# FoneAstra3_1.net
KiCad netlist of a schematic drawn in EAGLE
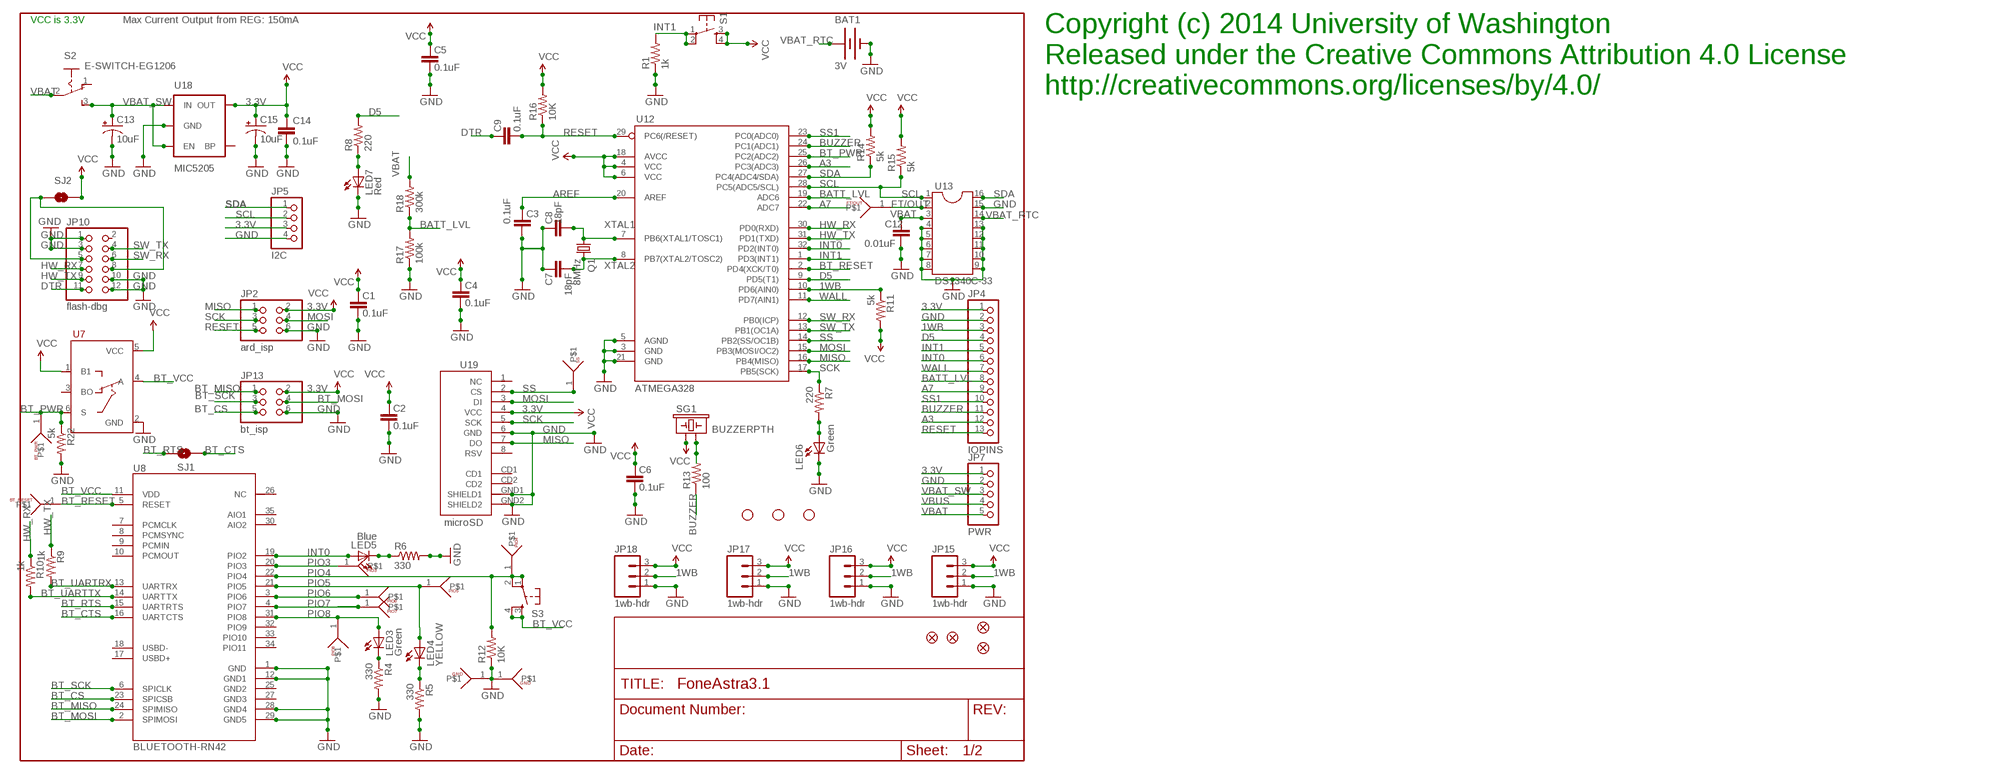
[diagram p0: schematic, sheet 1]
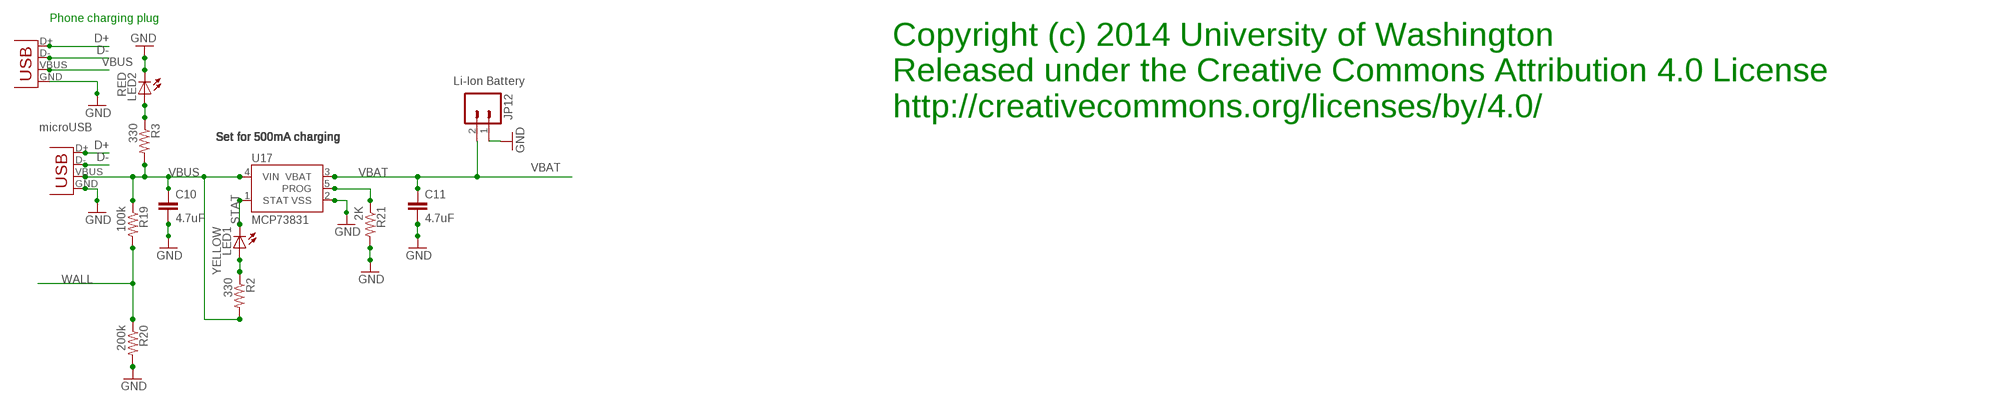
[diagram p1: schematic, sheet 2]

(export (version "E")
  (design (tool "Eeschema 10.0.6"))
  (components
    (comp (ref "$$U3")
      (value "BT_RESET")
      (footprint "eagle-import:TESTPOINT")
      (libsource (lib "eagle-import") (part "TESTPOINT"))
    )
    (comp (ref "$$U4")
      (value "PIO6")
      (footprint "eagle-import:TESTPOINT")
      (libsource (lib "eagle-import") (part "TESTPOINT"))
    )
    (comp (ref "$$U5")
      (value "PIO7")
      (footprint "eagle-import:TESTPOINT")
      (libsource (lib "eagle-import") (part "TESTPOINT"))
    )
    (comp (ref "$$U6")
      (value "GND")
      (footprint "eagle-import:TESTPOINT")
      (libsource (lib "eagle-import") (part "TESTPOINT"))
    )
    (comp (ref "$$U9")
      (value "PIO4")
      (footprint "eagle-import:TESTPOINT")
      (libsource (lib "eagle-import") (part "TESTPOINT"))
    )
    (comp (ref "$$U10")
      (value "PIO3")
      (footprint "eagle-import:TESTPOINT")
      (libsource (lib "eagle-import") (part "TESTPOINT"))
    )
    (comp (ref "$$U11")
      (value "PIO5")
      (footprint "eagle-import:TESTPOINT")
      (libsource (lib "eagle-import") (part "TESTPOINT"))
    )
    (comp (ref "$$U15")
      (value "FT/OUT")
      (footprint "eagle-import:TESTPOINT")
      (libsource (lib "eagle-import") (part "TESTPOINT"))
    )
    (comp (ref "$$U16")
      (value "GND")
      (footprint "eagle-import:TESTPOINT")
      (libsource (lib "eagle-import") (part "TESTPOINT"))
    )
    (comp (ref "BAT1")
      (value "3V")
      (footprint "eagle-import:BATTCON_12MM_CURVED")
      (libsource (lib "eagle-import") (part "BATTERY"))
    )
    (comp (ref "BT_PWR")
      (value "BT_PWR")
      (footprint "eagle-import:TESTPOINT")
      (libsource (lib "eagle-import") (part "TESTPOINT"))
    )
    (comp (ref "C1")
      (value "0.1uF")
      (footprint "eagle-import:0402-CAP")
      (libsource (lib "eagle-import") (part "CAP0402-CAP"))
    )
    (comp (ref "C2")
      (value "0.1uF")
      (footprint "eagle-import:0402-CAP")
      (libsource (lib "eagle-import") (part "CAP0402-CAP"))
    )
    (comp (ref "C3")
      (value "0.1uF")
      (footprint "eagle-import:0402-CAP")
      (libsource (lib "eagle-import") (part "CAP0402-CAP"))
    )
    (comp (ref "C4")
      (value "0.1uF")
      (footprint "eagle-import:0402-CAP")
      (libsource (lib "eagle-import") (part "CAP0402-CAP"))
    )
    (comp (ref "C5")
      (value "0.1uF")
      (footprint "eagle-import:0402-CAP")
      (libsource (lib "eagle-import") (part "CAP0402-CAP"))
    )
    (comp (ref "C6")
      (value "0.1uF")
      (footprint "eagle-import:0402-CAP")
      (libsource (lib "eagle-import") (part "CAP0402-CAP"))
    )
    (comp (ref "C7")
      (value "18pF")
      (footprint "eagle-import:0402-CAP")
      (libsource (lib "eagle-import") (part "CAP0402-CAP"))
    )
    (comp (ref "C8")
      (value "18pF")
      (footprint "eagle-import:0402-CAP")
      (libsource (lib "eagle-import") (part "CAP0402-CAP"))
    )
    (comp (ref "C9")
      (value "0.1uF")
      (footprint "eagle-import:0402-CAP")
      (libsource (lib "eagle-import") (part "CAP0402-CAP"))
    )
    (comp (ref "C12")
      (value "0.01uF")
      (footprint "eagle-import:0402-CAP")
      (libsource (lib "eagle-import") (part "CAP0402-CAP"))
    )
    (comp (ref "C13")
      (value "10uF")
      (footprint "eagle-import:EIA3216")
      (libsource (lib "eagle-import") (part "CAP_POL1206"))
    )
    (comp (ref "C14")
      (value "0.1uF")
      (footprint "eagle-import:0402-CAP")
      (libsource (lib "eagle-import") (part "CAP0402-CAP"))
    )
    (comp (ref "C15")
      (value "10uF")
      (footprint "eagle-import:EIA3216")
      (libsource (lib "eagle-import") (part "CAP_POL1206"))
    )
    (comp (ref "JP1")
      (value "SPARKFUN_FIDUCIAL1.5X3")
      (footprint "eagle-import:SPARKFUN_FIDUCIAL-1.5X3")
      (libsource (lib "eagle-import") (part "SPARKFUN_FIDUCIAL1.5X3"))
    )
    (comp (ref "JP2")
      (value "ard_isp")
      (footprint "eagle-import:2X03")
      (libsource (lib "eagle-import") (part "PINHD-2X3"))
    )
    (comp (ref "JP3")
      (value "STAND-OFFTIGHT")
      (footprint "eagle-import:STAND-OFF-TIGHT")
      (libsource (lib "eagle-import") (part "STAND-OFFTIGHT"))
    )
    (comp (ref "JP4")
      (value "IOPINS")
      (footprint "eagle-import:1X13M")
      (libsource (lib "eagle-import") (part "PINHD-1X13M"))
    )
    (comp (ref "JP5")
      (value "I2C")
      (footprint "eagle-import:1X04M")
      (libsource (lib "eagle-import") (part "PINHD-1X4M"))
    )
    (comp (ref "JP6")
      (value "STAND-OFFTIGHT")
      (footprint "eagle-import:STAND-OFF-TIGHT")
      (libsource (lib "eagle-import") (part "STAND-OFFTIGHT"))
    )
    (comp (ref "JP7")
      (value "PWR")
      (footprint "eagle-import:1X05M")
      (libsource (lib "eagle-import") (part "PINHD-1X5M"))
    )
    (comp (ref "JP8")
      (value "SPARKFUN_FIDUCIAL1.5X3")
      (footprint "eagle-import:SPARKFUN_FIDUCIAL-1.5X3")
      (libsource (lib "eagle-import") (part "SPARKFUN_FIDUCIAL1.5X3"))
    )
    (comp (ref "JP9")
      (value "STAND-OFFTIGHT")
      (footprint "eagle-import:STAND-OFF-TIGHT")
      (libsource (lib "eagle-import") (part "STAND-OFFTIGHT"))
    )
    (comp (ref "JP10")
      (value "flash-dbg")
      (footprint "eagle-import:2X06")
      (libsource (lib "eagle-import") (part "PINHD-2X6"))
    )
    (comp (ref "JP11")
      (value "SPARKFUN_FIDUCIAL1.5X3")
      (footprint "eagle-import:SPARKFUN_FIDUCIAL-1.5X3")
      (libsource (lib "eagle-import") (part "SPARKFUN_FIDUCIAL1.5X3"))
    )
    (comp (ref "JP13")
      (value "bt_isp")
      (footprint "eagle-import:2X03")
      (libsource (lib "eagle-import") (part "PINHD-2X3"))
    )
    (comp (ref "JP14")
      (value "SPARKFUN_FIDUCIAL1.5X3")
      (footprint "eagle-import:SPARKFUN_FIDUCIAL-1.5X3")
      (libsource (lib "eagle-import") (part "SPARKFUN_FIDUCIAL1.5X3"))
    )
    (comp (ref "JP15")
      (value "1wb-hdr")
      (footprint "eagle-import:JST-3-PTH")
      (libsource (lib "eagle-import") (part "M03JST-PTH"))
    )
    (comp (ref "JP16")
      (value "1wb-hdr")
      (footprint "eagle-import:JST-3-PTH")
      (libsource (lib "eagle-import") (part "M03JST-PTH"))
    )
    (comp (ref "JP17")
      (value "1wb-hdr")
      (footprint "eagle-import:JST-3-PTH")
      (libsource (lib "eagle-import") (part "M03JST-PTH"))
    )
    (comp (ref "JP18")
      (value "1wb-hdr")
      (footprint "eagle-import:JST-3-PTH")
      (libsource (lib "eagle-import") (part "M03JST-PTH"))
    )
    (comp (ref "LED3")
      (value "Green")
      (footprint "eagle-import:LED-0603")
      (libsource (lib "eagle-import") (part "LED0603"))
    )
    (comp (ref "LED4")
      (value "YELLOW")
      (footprint "eagle-import:LED-0603")
      (libsource (lib "eagle-import") (part "LED0603"))
    )
    (comp (ref "LED5")
      (value "Blue")
      (footprint "eagle-import:LED-0603")
      (libsource (lib "eagle-import") (part "LED0603"))
    )
    (comp (ref "LED6")
      (value "Green")
      (footprint "eagle-import:LED-0603")
      (libsource (lib "eagle-import") (part "LED0603"))
    )
    (comp (ref "LED7")
      (value "Red")
      (footprint "eagle-import:LED-0603")
      (libsource (lib "eagle-import") (part "LED0603"))
    )
    (comp (ref "PIO8")
      (value "PIO8")
      (footprint "eagle-import:TESTPOINT")
      (libsource (lib "eagle-import") (part "TESTPOINT"))
    )
    (comp (ref "Q1")
      (value "8MHz")
      (footprint "eagle-import:HC49_S")
      (libsource (lib "eagle-import") (part "CRYSTALHC49S"))
    )
    (comp (ref "R1")
      (value "1k")
      (footprint "eagle-import:0402-RES")
      (libsource (lib "eagle-import") (part "RESISTOR0402-RES"))
    )
    (comp (ref "R4")
      (value "330")
      (footprint "eagle-import:0402-RES")
      (libsource (lib "eagle-import") (part "RESISTOR0402-RES"))
    )
    (comp (ref "R5")
      (value "330")
      (footprint "eagle-import:0402-RES")
      (libsource (lib "eagle-import") (part "RESISTOR0402-RES"))
    )
    (comp (ref "R6")
      (value "330")
      (footprint "eagle-import:0402-RES")
      (libsource (lib "eagle-import") (part "RESISTOR0402-RES"))
    )
    (comp (ref "R7")
      (value "220")
      (footprint "eagle-import:0402-RES")
      (libsource (lib "eagle-import") (part "RESISTOR0402-RES"))
    )
    (comp (ref "R8")
      (value "220")
      (footprint "eagle-import:0402-RES")
      (libsource (lib "eagle-import") (part "RESISTOR0402-RES"))
    )
    (comp (ref "R9")
      (value "1k")
      (footprint "eagle-import:0402-RES")
      (libsource (lib "eagle-import") (part "RESISTOR0402-RES"))
    )
    (comp (ref "R10")
      (value "1k")
      (footprint "eagle-import:0402-RES")
      (libsource (lib "eagle-import") (part "RESISTOR0402-RES"))
    )
    (comp (ref "R11")
      (value "5k")
      (footprint "eagle-import:0402-RES")
      (libsource (lib "eagle-import") (part "RESISTOR0402-RES"))
    )
    (comp (ref "R12")
      (value "10K")
      (footprint "eagle-import:0402-RES")
      (libsource (lib "eagle-import") (part "RESISTOR0402-RES"))
    )
    (comp (ref "R13")
      (value "100")
      (footprint "eagle-import:0402-RES")
      (libsource (lib "eagle-import") (part "RESISTOR0402-RES"))
    )
    (comp (ref "R14")
      (value "5k")
      (footprint "eagle-import:0402-RES")
      (libsource (lib "eagle-import") (part "RESISTOR0402-RES"))
    )
    (comp (ref "R15")
      (value "5k")
      (footprint "eagle-import:0402-RES")
      (libsource (lib "eagle-import") (part "RESISTOR0402-RES"))
    )
    (comp (ref "R16")
      (value "10K")
      (footprint "eagle-import:0402-RES")
      (libsource (lib "eagle-import") (part "RESISTOR0402-RES"))
    )
    (comp (ref "R17")
      (value "100k")
      (footprint "eagle-import:0402-RES")
      (libsource (lib "eagle-import") (part "RESISTOR0402-RES"))
    )
    (comp (ref "R18")
      (value "300k")
      (footprint "eagle-import:0402-RES")
      (libsource (lib "eagle-import") (part "RESISTOR0402-RES"))
    )
    (comp (ref "R22")
      (value "5k")
      (footprint "eagle-import:0402-RES")
      (libsource (lib "eagle-import") (part "RESISTOR0402-RES"))
    )
    (comp (ref "S1")
      (value "switch")
      (footprint "eagle-import:SPARKFUN_TACTILE-PTH")
      (libsource (lib "eagle-import") (part "SPARKFUN_TAC_SWITCHPTH"))
    )
    (comp (ref "S2")
      (value "E-SWITCH-EG1206")
      (footprint "eagle-import:EG1206")
      (libsource (lib "eagle-import") (part "E-SWITCH-EG1206"))
    )
    (comp (ref "S3")
      (value "Reset")
      (footprint "eagle-import:TACTILE_SWITCH_SMD")
      (libsource (lib "eagle-import") (part "TAC_SWITCHSMD"))
    )
    (comp (ref "SG1")
      (value "BUZZERPTH")
      (footprint "eagle-import:BUZZER-12MM")
      (libsource (lib "eagle-import") (part "BUZZERPTH"))
    )
    (comp (ref "SJ1")
      (value "SOLDERJUMPERNC2")
      (footprint "eagle-import:SJ_2S-NOTRACE")
      (libsource (lib "eagle-import") (part "SOLDERJUMPERNC2"))
    )
    (comp (ref "SJ2")
      (value "SOLDERJUMPERNC2")
      (footprint "eagle-import:SJ_2S-NOTRACE")
      (libsource (lib "eagle-import") (part "SOLDERJUMPERNC2"))
    )
    (comp (ref "SS")
      (value "SS")
      (footprint "eagle-import:TESTPOINT")
      (libsource (lib "eagle-import") (part "TESTPOINT"))
    )
    (comp (ref "U7")
      (value "FSA4157AP6X")
      (footprint "eagle-import:SC70-6")
      (libsource (lib "eagle-import") (part "FSA4157AP6X"))
    )
    (comp (ref "U8")
      (value "BLUETOOTH-RN42")
      (footprint "eagle-import:RN41")
      (libsource (lib "eagle-import") (part "BLUETOOTH-RN41{dblquote}"))
    )
    (comp (ref "U12")
      (value "ATMEGA328")
      (footprint "eagle-import:TQFP32-08")
      (libsource (lib "eagle-import") (part "ATMEGA168"))
    )
    (comp (ref "U13")
      (value "DS1340C-33")
      (footprint "eagle-import:SO16L")
      (libsource (lib "eagle-import") (part "DS1340C-33"))
    )
    (comp (ref "U18")
      (value "MIC5205")
      (footprint "eagle-import:SOT23-5")
      (libsource (lib "eagle-import") (part "V_REG_LDOSMD"))
    )
    (comp (ref "U19")
      (value "microSD")
      (footprint "eagle-import:MICRO-SD-SOCKET-PP")
      (libsource (lib "eagle-import") (part "USD-SOCKETSMD"))
    )
    (comp (ref "C10")
      (value "4.7uF")
      (footprint "eagle-import:0402-CAP")
      (libsource (lib "eagle-import") (part "CAP0402-CAP"))
    )
    (comp (ref "C11")
      (value "4.7uF")
      (footprint "eagle-import:0402-CAP")
      (libsource (lib "eagle-import") (part "CAP0402-CAP"))
    )
    (comp (ref "JP12")
      (value "Li-Ion Battery")
      (footprint "eagle-import:SPARKFUN_JST-2-PTH")
      (libsource (lib "eagle-import") (part "SPARKFUN_M02JST-PTH-2"))
    )
    (comp (ref "LED1")
      (value "YELLOW")
      (footprint "eagle-import:LED-0603")
      (libsource (lib "eagle-import") (part "LED0603"))
    )
    (comp (ref "LED2")
      (value "RED")
      (footprint "eagle-import:LED-0603")
      (libsource (lib "eagle-import") (part "LED0603"))
    )
    (comp (ref "R2")
      (value "330")
      (footprint "eagle-import:0402-RES")
      (libsource (lib "eagle-import") (part "RESISTOR0402-RES"))
    )
    (comp (ref "R3")
      (value "330")
      (footprint "eagle-import:0402-RES")
      (libsource (lib "eagle-import") (part "RESISTOR0402-RES"))
    )
    (comp (ref "R19")
      (value "100k")
      (footprint "eagle-import:0402-RES")
      (libsource (lib "eagle-import") (part "RESISTOR0402-RES"))
    )
    (comp (ref "R20")
      (value "200k")
      (footprint "eagle-import:0402-RES")
      (libsource (lib "eagle-import") (part "RESISTOR0402-RES"))
    )
    (comp (ref "R21")
      (value "2K")
      (footprint "eagle-import:0402-RES")
      (libsource (lib "eagle-import") (part "RESISTOR0402-RES"))
    )
    (comp (ref "U17")
      (value "MCP73831")
      (footprint "eagle-import:SOT23-5")
      (libsource (lib "eagle-import") (part "MCP73831"))
    )
    (comp (ref "X1")
      (value "Micro USB")
      (footprint "eagle-import:USB-MICROB")
      (libsource (lib "eagle-import") (part "USB-MICROB"))
    )
    (comp (ref "X2")
      (value "Micro USB")
      (footprint "eagle-import:USB-MICROB")
      (libsource (lib "eagle-import") (part "USB-MICROB"))
    )
  )
  (nets
    (net (code "1") (name "1WB") (class "Default")
      (node (ref "JP15") (pin "2") (pinfunction "2_2") (pintype "passive"))
      (node (ref "JP16") (pin "2") (pinfunction "2_2") (pintype "passive"))
      (node (ref "JP17") (pin "2") (pinfunction "2_2") (pintype "passive"))
      (node (ref "JP18") (pin "2") (pinfunction "2_2") (pintype "passive"))
      (node (ref "JP4") (pin "3") (pinfunction "3_3") (pintype "passive"))
      (node (ref "R11") (pin "1") (pinfunction "1_1") (pintype "passive"))
      (node (ref "U12") (pin "10") (pinfunction "PD6(AIN0)_10") (pintype "bidirectional"))
    )
    (net (code "2") (name "3.3V") (class "Default")
      (node (ref "C1") (pin "2") (pinfunction "2_2") (pintype "passive"))
      (node (ref "C14") (pin "1") (pinfunction "1_1") (pintype "passive"))
      (node (ref "C15") (pin "A") (pinfunction "+_A") (pintype "passive"))
      (node (ref "C2") (pin "2") (pinfunction "2_2") (pintype "passive"))
      (node (ref "C4") (pin "2") (pinfunction "2_2") (pintype "passive"))
      (node (ref "C5") (pin "2") (pinfunction "2_2") (pintype "passive"))
      (node (ref "C6") (pin "2") (pinfunction "2_2") (pintype "passive"))
      (node (ref "JP13") (pin "2") (pinfunction "2_2") (pintype "passive"))
      (node (ref "JP15") (pin "3") (pinfunction "3_3") (pintype "passive"))
      (node (ref "JP16") (pin "3") (pinfunction "3_3") (pintype "passive"))
      (node (ref "JP17") (pin "3") (pinfunction "3_3") (pintype "passive"))
      (node (ref "JP18") (pin "3") (pinfunction "3_3") (pintype "passive"))
      (node (ref "JP2") (pin "2") (pinfunction "2_2") (pintype "passive"))
      (node (ref "JP4") (pin "1") (pinfunction "1_1") (pintype "passive"))
      (node (ref "JP5") (pin "3") (pinfunction "3_3") (pintype "passive"))
      (node (ref "JP7") (pin "1") (pinfunction "1_1") (pintype "passive"))
      (node (ref "R11") (pin "2") (pinfunction "2_2") (pintype "passive"))
      (node (ref "R14") (pin "2") (pinfunction "2_2") (pintype "passive"))
      (node (ref "R15") (pin "2") (pinfunction "2_2") (pintype "passive"))
      (node (ref "R16") (pin "2") (pinfunction "2_2") (pintype "passive"))
      (node (ref "S1") (pin "3") (pinfunction "3_3") (pintype "passive"))
      (node (ref "S1") (pin "4") (pinfunction "4_4") (pintype "passive"))
      (node (ref "SG1") (pin "+") (pinfunction "1_+") (pintype "passive"))
      (node (ref "SJ2") (pin "1") (pinfunction "1_1") (pintype "passive"))
      (node (ref "U12") (pin "18") (pinfunction "AVCC_18") (pintype "bidirectional"))
      (node (ref "U12") (pin "4") (pinfunction "VCC_4") (pintype "bidirectional"))
      (node (ref "U12") (pin "6") (pinfunction "VCC_6") (pintype "bidirectional"))
      (node (ref "U18") (pin "5") (pinfunction "OUT_5") (pintype "passive"))
      (node (ref "U19") (pin "4") (pinfunction "VCC_4") (pintype "bidirectional"))
      (node (ref "U7") (pin "1") (pinfunction "B1_1") (pintype "passive"))
      (node (ref "U7") (pin "5") (pinfunction "VCC_5") (pintype "power_in"))
    )
    (net (code "3") (name "A3") (class "Default")
      (node (ref "JP4") (pin "12") (pinfunction "12_12") (pintype "passive"))
      (node (ref "U12") (pin "26") (pinfunction "PC3(ADC3)_26") (pintype "bidirectional"))
    )
    (net (code "4") (name "A7") (class "Default")
      (node (ref "JP4") (pin "9") (pinfunction "9_9") (pintype "passive"))
      (node (ref "U12") (pin "22") (pinfunction "ADC7_22") (pintype "bidirectional"))
    )
    (net (code "5") (name "AREF") (class "Default")
      (node (ref "C3") (pin "2") (pinfunction "2_2") (pintype "passive"))
      (node (ref "U12") (pin "20") (pinfunction "AREF_20") (pintype "bidirectional"))
    )
    (net (code "6") (name "BATT_LVL") (class "Default")
      (node (ref "JP4") (pin "8") (pinfunction "8_8") (pintype "passive"))
      (node (ref "R17") (pin "2") (pinfunction "2_2") (pintype "passive"))
      (node (ref "R18") (pin "1") (pinfunction "1_1") (pintype "passive"))
      (node (ref "U12") (pin "19") (pinfunction "ADC6_19") (pintype "bidirectional"))
    )
    (net (code "7") (name "BT_CS") (class "Default")
      (node (ref "JP13") (pin "5") (pinfunction "5_5") (pintype "passive"))
      (node (ref "U8") (pin "23") (pinfunction "SPICSB_23") (pintype "bidirectional"))
    )
    (net (code "8") (name "BT_CTS") (class "Default")
      (node (ref "SJ1") (pin "1") (pinfunction "1_1") (pintype "passive"))
      (node (ref "U8") (pin "16") (pinfunction "UARTCTS_16") (pintype "bidirectional"))
    )
    (net (code "9") (name "BT_MISO") (class "Default")
      (node (ref "JP13") (pin "1") (pinfunction "1_1") (pintype "passive"))
      (node (ref "U8") (pin "24") (pinfunction "SPIMISO_24") (pintype "bidirectional"))
    )
    (net (code "10") (name "BT_MOSI") (class "Default")
      (node (ref "JP13") (pin "4") (pinfunction "4_4") (pintype "passive"))
      (node (ref "U8") (pin "2") (pinfunction "SPIMOSI_2") (pintype "bidirectional"))
    )
    (net (code "11") (name "BT_PWR") (class "Default")
      (node (ref "BT_PWR") (pin "1") (pinfunction "P$1_1") (pintype "bidirectional"))
      (node (ref "R22") (pin "1") (pinfunction "1_1") (pintype "passive"))
      (node (ref "U12") (pin "25") (pinfunction "PC2(ADC2)_25") (pintype "bidirectional"))
      (node (ref "U7") (pin "6") (pinfunction "S_6") (pintype "bidirectional"))
    )
    (net (code "12") (name "BT_RESET") (class "Default")
      (node (ref "$$U3") (pin "1") (pinfunction "P$1_1") (pintype "bidirectional"))
      (node (ref "U12") (pin "2") (pinfunction "PD4(XCK/T0)_2") (pintype "bidirectional"))
      (node (ref "U8") (pin "5") (pinfunction "RESET_5") (pintype "bidirectional"))
    )
    (net (code "13") (name "BT_RTS") (class "Default")
      (node (ref "SJ1") (pin "2") (pinfunction "2_2") (pintype "passive"))
      (node (ref "U8") (pin "15") (pinfunction "UARTRTS_15") (pintype "bidirectional"))
    )
    (net (code "14") (name "BT_SCK") (class "Default")
      (node (ref "JP13") (pin "3") (pinfunction "3_3") (pintype "passive"))
      (node (ref "U8") (pin "6") (pinfunction "SPICLK_6") (pintype "bidirectional"))
    )
    (net (code "15") (name "BT_UARTRX") (class "Default")
      (node (ref "R9") (pin "2") (pinfunction "2_2") (pintype "passive"))
      (node (ref "U8") (pin "13") (pinfunction "UARTRX_13") (pintype "bidirectional"))
    )
    (net (code "16") (name "BT_UARTTX") (class "Default")
      (node (ref "R10") (pin "2") (pinfunction "2_2") (pintype "passive"))
      (node (ref "U8") (pin "14") (pinfunction "UARTTX_14") (pintype "bidirectional"))
    )
    (net (code "17") (name "BT_VCC") (class "Default")
      (node (ref "S3") (pin "3") (pinfunction "3_3") (pintype "passive"))
      (node (ref "S3") (pin "4") (pinfunction "4_4") (pintype "passive"))
      (node (ref "U7") (pin "4") (pinfunction "A_4") (pintype "passive"))
      (node (ref "U8") (pin "11") (pinfunction "VDD_11") (pintype "bidirectional"))
    )
    (net (code "18") (name "BUZZER") (class "Default")
      (node (ref "JP4") (pin "11") (pinfunction "11_11") (pintype "passive"))
      (node (ref "R13") (pin "1") (pinfunction "1_1") (pintype "passive"))
      (node (ref "U12") (pin "24") (pinfunction "PC1(ADC1)_24") (pintype "bidirectional"))
    )
    (net (code "19") (name "D+") (class "Default")
      (node (ref "X1") (pin "D+") (pinfunction "D+_D+") (pintype "bidirectional"))
      (node (ref "X2") (pin "D+") (pinfunction "D+_D+") (pintype "bidirectional"))
    )
    (net (code "20") (name "D-") (class "Default")
      (node (ref "X1") (pin "D-") (pinfunction "D-_D-") (pintype "bidirectional"))
      (node (ref "X2") (pin "D-") (pinfunction "D-_D-") (pintype "bidirectional"))
    )
    (net (code "21") (name "D5") (class "Default")
      (node (ref "JP4") (pin "4") (pinfunction "4_4") (pintype "passive"))
      (node (ref "R8") (pin "2") (pinfunction "2_2") (pintype "passive"))
      (node (ref "U12") (pin "9") (pinfunction "PD5(T1)_9") (pintype "bidirectional"))
    )
    (net (code "22") (name "DTR") (class "Default")
      (node (ref "C9") (pin "2") (pinfunction "2_2") (pintype "passive"))
      (node (ref "JP10") (pin "11") (pinfunction "11_11") (pintype "passive"))
    )
    (net (code "23") (name "FT{slash}OUT") (class "Default")
      (node (ref "$$U15") (pin "1") (pinfunction "P$1_1") (pintype "bidirectional"))
      (node (ref "U13") (pin "2") (pinfunction "2_2") (pintype "passive"))
    )
    (net (code "24") (name "GND") (class "Default")
      (node (ref "$$U16") (pin "1") (pinfunction "P$1_1") (pintype "bidirectional"))
      (node (ref "$$U6") (pin "1") (pinfunction "P$1_1") (pintype "bidirectional"))
      (node (ref "BAT1") (pin "GND") (pinfunction "-_GND") (pintype "power_in"))
      (node (ref "C1") (pin "1") (pinfunction "1_1") (pintype "passive"))
      (node (ref "C10") (pin "2") (pinfunction "2_2") (pintype "passive"))
      (node (ref "C11") (pin "2") (pinfunction "2_2") (pintype "passive"))
      (node (ref "C12") (pin "1") (pinfunction "1_1") (pintype "passive"))
      (node (ref "C13") (pin "C") (pinfunction "-_C") (pintype "passive"))
      (node (ref "C14") (pin "2") (pinfunction "2_2") (pintype "passive"))
      (node (ref "C15") (pin "C") (pinfunction "-_C") (pintype "passive"))
      (node (ref "C2") (pin "1") (pinfunction "1_1") (pintype "passive"))
      (node (ref "C3") (pin "1") (pinfunction "1_1") (pintype "passive"))
      (node (ref "C4") (pin "1") (pinfunction "1_1") (pintype "passive"))
      (node (ref "C5") (pin "1") (pinfunction "1_1") (pintype "passive"))
      (node (ref "C6") (pin "1") (pinfunction "1_1") (pintype "passive"))
      (node (ref "C7") (pin "2") (pinfunction "2_2") (pintype "passive"))
      (node (ref "C8") (pin "2") (pinfunction "2_2") (pintype "passive"))
      (node (ref "JP10") (pin "1") (pinfunction "1_1") (pintype "passive"))
      (node (ref "JP10") (pin "10") (pinfunction "10_10") (pintype "passive"))
      (node (ref "JP10") (pin "12") (pinfunction "12_12") (pintype "passive"))
      (node (ref "JP10") (pin "3") (pinfunction "3_3") (pintype "passive"))
      (node (ref "JP12") (pin "1") (pinfunction "1_1") (pintype "passive"))
      (node (ref "JP13") (pin "6") (pinfunction "6_6") (pintype "passive"))
      (node (ref "JP15") (pin "1") (pinfunction "1_1") (pintype "passive"))
      (node (ref "JP16") (pin "1") (pinfunction "1_1") (pintype "passive"))
      (node (ref "JP17") (pin "1") (pinfunction "1_1") (pintype "passive"))
      (node (ref "JP18") (pin "1") (pinfunction "1_1") (pintype "passive"))
      (node (ref "JP2") (pin "6") (pinfunction "6_6") (pintype "passive"))
      (node (ref "JP4") (pin "2") (pinfunction "2_2") (pintype "passive"))
      (node (ref "JP5") (pin "4") (pinfunction "4_4") (pintype "passive"))
      (node (ref "JP7") (pin "2") (pinfunction "2_2") (pintype "passive"))
      (node (ref "LED2") (pin "C") (pinfunction "C_C") (pintype "passive"))
      (node (ref "LED6") (pin "C") (pinfunction "C_C") (pintype "passive"))
      (node (ref "LED7") (pin "C") (pinfunction "C_C") (pintype "passive"))
      (node (ref "R1") (pin "1") (pinfunction "1_1") (pintype "passive"))
      (node (ref "R12") (pin "1") (pinfunction "1_1") (pintype "passive"))
      (node (ref "R17") (pin "1") (pinfunction "1_1") (pintype "passive"))
      (node (ref "R20") (pin "2") (pinfunction "2_2") (pintype "passive"))
      (node (ref "R21") (pin "2") (pinfunction "2_2") (pintype "passive"))
      (node (ref "R22") (pin "2") (pinfunction "2_2") (pintype "passive"))
      (node (ref "R4") (pin "2") (pinfunction "2_2") (pintype "passive"))
      (node (ref "R5") (pin "2") (pinfunction "2_2") (pintype "passive"))
      (node (ref "R6") (pin "2") (pinfunction "2_2") (pintype "passive"))
      (node (ref "U12") (pin "21") (pinfunction "GND_21") (pintype "bidirectional"))
      (node (ref "U12") (pin "3") (pinfunction "GND_3") (pintype "bidirectional"))
      (node (ref "U12") (pin "5") (pinfunction "AGND_5") (pintype "bidirectional"))
      (node (ref "U13") (pin "10") (pinfunction "10_10") (pintype "passive"))
      (node (ref "U13") (pin "11") (pinfunction "11_11") (pintype "passive"))
      (node (ref "U13") (pin "12") (pinfunction "12_12") (pintype "passive"))
      (node (ref "U13") (pin "13") (pinfunction "13_13") (pintype "passive"))
      (node (ref "U13") (pin "15") (pinfunction "15_15") (pintype "passive"))
      (node (ref "U13") (pin "4") (pinfunction "4_4") (pintype "passive"))
      (node (ref "U13") (pin "5") (pinfunction "5_5") (pintype "passive"))
      (node (ref "U13") (pin "6") (pinfunction "6_6") (pintype "passive"))
      (node (ref "U13") (pin "7") (pinfunction "7_7") (pintype "passive"))
      (node (ref "U13") (pin "8") (pinfunction "8_8") (pintype "passive"))
      (node (ref "U13") (pin "9") (pinfunction "9_9") (pintype "passive"))
      (node (ref "U17") (pin "2") (pinfunction "VSS_2") (pintype "power_in"))
      (node (ref "U18") (pin "2") (pinfunction "GND_2") (pintype "input"))
      (node (ref "U19") (pin "6") (pinfunction "GND_6") (pintype "bidirectional"))
      (node (ref "U19") (pin "GND1") (pinfunction "SHIELD1_GND1") (pintype "bidirectional"))
      (node (ref "U19") (pin "GND2") (pinfunction "SHIELD2_GND2") (pintype "bidirectional"))
      (node (ref "U7") (pin "2") (pinfunction "GND_2") (pintype "bidirectional"))
      (node (ref "U8") (pin "1") (pinfunction "GND_1") (pintype "bidirectional"))
      (node (ref "U8") (pin "12") (pinfunction "GND1_12") (pintype "bidirectional"))
      (node (ref "U8") (pin "28") (pinfunction "GND4_28") (pintype "bidirectional"))
      (node (ref "U8") (pin "29") (pinfunction "GND5_29") (pintype "bidirectional"))
      (node (ref "X1") (pin "GND") (pinfunction "GND_GND") (pintype "bidirectional"))
      (node (ref "X2") (pin "GND") (pinfunction "GND_GND") (pintype "bidirectional"))
    )
    (net (code "25") (name "HW_RX") (class "Default")
      (node (ref "JP10") (pin "7") (pinfunction "7_7") (pintype "passive"))
      (node (ref "R10") (pin "1") (pinfunction "1_1") (pintype "passive"))
      (node (ref "U12") (pin "30") (pinfunction "PD0(RXD)_30") (pintype "bidirectional"))
    )
    (net (code "26") (name "HW_TX") (class "Default")
      (node (ref "JP10") (pin "9") (pinfunction "9_9") (pintype "passive"))
      (node (ref "R9") (pin "1") (pinfunction "1_1") (pintype "passive"))
      (node (ref "U12") (pin "31") (pinfunction "PD1(TXD)_31") (pintype "bidirectional"))
    )
    (net (code "27") (name "INT0") (class "Default")
      (node (ref "JP4") (pin "6") (pinfunction "6_6") (pintype "passive"))
      (node (ref "LED5") (pin "A") (pinfunction "A_A") (pintype "passive"))
      (node (ref "U12") (pin "32") (pinfunction "PD2(INT0)_32") (pintype "bidirectional"))
      (node (ref "U8") (pin "19") (pinfunction "PIO2_19") (pintype "bidirectional"))
    )
    (net (code "28") (name "INT1") (class "Default")
      (node (ref "JP4") (pin "5") (pinfunction "5_5") (pintype "passive"))
      (node (ref "R1") (pin "2") (pinfunction "2_2") (pintype "passive"))
      (node (ref "S1") (pin "1") (pinfunction "1_1") (pintype "passive"))
      (node (ref "S1") (pin "2") (pinfunction "2_2") (pintype "passive"))
      (node (ref "U12") (pin "1") (pinfunction "PD3(INT1)_1") (pintype "bidirectional"))
    )
    (net (code "29") (name "MISO") (class "Default")
      (node (ref "JP2") (pin "1") (pinfunction "1_1") (pintype "passive"))
      (node (ref "U12") (pin "16") (pinfunction "PB4(MISO)_16") (pintype "bidirectional"))
      (node (ref "U19") (pin "7") (pinfunction "DO_7") (pintype "bidirectional"))
    )
    (net (code "30") (name "MOSI") (class "Default")
      (node (ref "JP2") (pin "4") (pinfunction "4_4") (pintype "passive"))
      (node (ref "U12") (pin "15") (pinfunction "PB3(MOSI/OC2)_15") (pintype "bidirectional"))
      (node (ref "U19") (pin "3") (pinfunction "DI_3") (pintype "bidirectional"))
    )
    (net (code "31") (name "Net-(JP10-Pad5)") (class "Default")
      (node (ref "JP10") (pin "5") (pinfunction "5_5") (pintype "passive"))
      (node (ref "JP10") (pin "8") (pinfunction "8_8") (pintype "passive"))
      (node (ref "SJ2") (pin "2") (pinfunction "2_2") (pintype "passive"))
    )
    (net (code "32") (name "Net-(LED1-PadA)") (class "Default")
      (node (ref "LED1") (pin "A") (pinfunction "A_A") (pintype "passive"))
      (node (ref "R2") (pin "1") (pinfunction "1_1") (pintype "passive"))
    )
    (net (code "33") (name "Net-(LED2-PadA)") (class "Default")
      (node (ref "LED2") (pin "A") (pinfunction "A_A") (pintype "passive"))
      (node (ref "R3") (pin "1") (pinfunction "1_1") (pintype "passive"))
    )
    (net (code "34") (name "Net-(LED3-PadC)") (class "Default")
      (node (ref "LED3") (pin "C") (pinfunction "C_C") (pintype "passive"))
      (node (ref "R4") (pin "1") (pinfunction "1_1") (pintype "passive"))
    )
    (net (code "35") (name "Net-(LED4-PadC)") (class "Default")
      (node (ref "LED4") (pin "C") (pinfunction "C_C") (pintype "passive"))
      (node (ref "R5") (pin "1") (pinfunction "1_1") (pintype "passive"))
    )
    (net (code "36") (name "Net-(LED5-PadC)") (class "Default")
      (node (ref "LED5") (pin "C") (pinfunction "C_C") (pintype "passive"))
      (node (ref "R6") (pin "1") (pinfunction "1_1") (pintype "passive"))
    )
    (net (code "37") (name "Net-(LED6-PadA)") (class "Default")
      (node (ref "LED6") (pin "A") (pinfunction "A_A") (pintype "passive"))
      (node (ref "R7") (pin "2") (pinfunction "2_2") (pintype "passive"))
    )
    (net (code "38") (name "Net-(LED7-PadA)") (class "Default")
      (node (ref "LED7") (pin "A") (pinfunction "A_A") (pintype "passive"))
      (node (ref "R8") (pin "1") (pinfunction "1_1") (pintype "passive"))
    )
    (net (code "39") (name "Net-(SG1-2)") (class "Default")
      (node (ref "R13") (pin "2") (pinfunction "2_2") (pintype "passive"))
      (node (ref "SG1") (pin "-") (pinfunction "2_-") (pintype "passive"))
    )
    (net (code "40") (name "Net-(U17-PROG)") (class "Default")
      (node (ref "R21") (pin "1") (pinfunction "1_1") (pintype "passive"))
      (node (ref "U17") (pin "5") (pinfunction "PROG_5") (pintype "input"))
    )
    (net (code "41") (name "PIO3") (class "Default")
      (node (ref "$$U10") (pin "1") (pinfunction "P$1_1") (pintype "bidirectional"))
      (node (ref "U8") (pin "20") (pinfunction "PIO3_20") (pintype "bidirectional"))
    )
    (net (code "42") (name "PIO4") (class "Default")
      (node (ref "$$U9") (pin "1") (pinfunction "P$1_1") (pintype "bidirectional"))
      (node (ref "R12") (pin "2") (pinfunction "2_2") (pintype "passive"))
      (node (ref "S3") (pin "1") (pinfunction "1_1") (pintype "passive"))
      (node (ref "S3") (pin "2") (pinfunction "2_2") (pintype "passive"))
      (node (ref "U8") (pin "22") (pinfunction "PIO4_22") (pintype "bidirectional"))
    )
    (net (code "43") (name "PIO5") (class "Default")
      (node (ref "$$U11") (pin "1") (pinfunction "P$1_1") (pintype "bidirectional"))
      (node (ref "LED4") (pin "A") (pinfunction "A_A") (pintype "passive"))
      (node (ref "U8") (pin "21") (pinfunction "PIO5_21") (pintype "bidirectional"))
    )
    (net (code "44") (name "PIO6") (class "Default")
      (node (ref "$$U4") (pin "1") (pinfunction "P$1_1") (pintype "bidirectional"))
      (node (ref "U8") (pin "3") (pinfunction "PIO6_3") (pintype "bidirectional"))
    )
    (net (code "45") (name "PIO7") (class "Default")
      (node (ref "$$U5") (pin "1") (pinfunction "P$1_1") (pintype "bidirectional"))
      (node (ref "U8") (pin "4") (pinfunction "PIO7_4") (pintype "bidirectional"))
    )
    (net (code "46") (name "PIO8") (class "Default")
      (node (ref "LED3") (pin "A") (pinfunction "A_A") (pintype "passive"))
      (node (ref "PIO8") (pin "1") (pinfunction "P$1_1") (pintype "bidirectional"))
      (node (ref "U8") (pin "31") (pinfunction "PIO8_31") (pintype "bidirectional"))
    )
    (net (code "47") (name "RESET") (class "Default")
      (node (ref "C9") (pin "1") (pinfunction "1_1") (pintype "passive"))
      (node (ref "JP2") (pin "5") (pinfunction "5_5") (pintype "passive"))
      (node (ref "JP4") (pin "13") (pinfunction "13_13") (pintype "passive"))
      (node (ref "R16") (pin "1") (pinfunction "1_1") (pintype "passive"))
      (node (ref "U12") (pin "29") (pinfunction "PC6(/RESET)_29") (pintype "bidirectional"))
    )
    (net (code "48") (name "SCK") (class "Default")
      (node (ref "JP2") (pin "3") (pinfunction "3_3") (pintype "passive"))
      (node (ref "R7") (pin "1") (pinfunction "1_1") (pintype "passive"))
      (node (ref "U12") (pin "17") (pinfunction "PB5(SCK)_17") (pintype "bidirectional"))
      (node (ref "U19") (pin "5") (pinfunction "SCK_5") (pintype "bidirectional"))
    )
    (net (code "49") (name "SCL") (class "Default")
      (node (ref "JP5") (pin "2") (pinfunction "2_2") (pintype "passive"))
      (node (ref "R15") (pin "1") (pinfunction "1_1") (pintype "passive"))
      (node (ref "U12") (pin "28") (pinfunction "PC5(ADC5/SCL)_28") (pintype "bidirectional"))
      (node (ref "U13") (pin "1") (pinfunction "1_1") (pintype "passive"))
    )
    (net (code "50") (name "SDA") (class "Default")
      (node (ref "JP5") (pin "1") (pinfunction "1_1") (pintype "passive"))
      (node (ref "R14") (pin "1") (pinfunction "1_1") (pintype "passive"))
      (node (ref "U12") (pin "27") (pinfunction "PC4(ADC4/SDA)_27") (pintype "bidirectional"))
      (node (ref "U13") (pin "16") (pinfunction "16_16") (pintype "passive"))
    )
    (net (code "51") (name "SS") (class "Default")
      (node (ref "SS") (pin "1") (pinfunction "P$1_1") (pintype "bidirectional"))
      (node (ref "U12") (pin "14") (pinfunction "PB2(SS/OC1B)_14") (pintype "bidirectional"))
      (node (ref "U19") (pin "2") (pinfunction "CS_2") (pintype "bidirectional"))
    )
    (net (code "52") (name "SS1") (class "Default")
      (node (ref "JP4") (pin "10") (pinfunction "10_10") (pintype "passive"))
      (node (ref "U12") (pin "23") (pinfunction "PC0(ADC0)_23") (pintype "bidirectional"))
    )
    (net (code "53") (name "STAT") (class "Default")
      (node (ref "LED1") (pin "C") (pinfunction "C_C") (pintype "passive"))
      (node (ref "U17") (pin "1") (pinfunction "STAT_1") (pintype "output"))
    )
    (net (code "54") (name "SW_RX") (class "Default")
      (node (ref "JP10") (pin "6") (pinfunction "6_6") (pintype "passive"))
      (node (ref "U12") (pin "12") (pinfunction "PB0(ICP)_12") (pintype "bidirectional"))
    )
    (net (code "55") (name "SW_TX") (class "Default")
      (node (ref "JP10") (pin "4") (pinfunction "4_4") (pintype "passive"))
      (node (ref "U12") (pin "13") (pinfunction "PB1(OC1A)_13") (pintype "bidirectional"))
    )
    (net (code "56") (name "VBAT") (class "Default")
      (node (ref "C11") (pin "1") (pinfunction "1_1") (pintype "passive"))
      (node (ref "C12") (pin "2") (pinfunction "2_2") (pintype "passive"))
      (node (ref "JP12") (pin "2") (pinfunction "2_2") (pintype "passive"))
      (node (ref "JP7") (pin "5") (pinfunction "5_5") (pintype "passive"))
      (node (ref "R18") (pin "2") (pinfunction "2_2") (pintype "passive"))
      (node (ref "S2") (pin "2") (pinfunction "P_2") (pintype "passive"))
      (node (ref "U13") (pin "3") (pinfunction "3_3") (pintype "passive"))
      (node (ref "U17") (pin "3") (pinfunction "VBAT_3") (pintype "power_in"))
    )
    (net (code "57") (name "VBAT_RTC") (class "Default")
      (node (ref "BAT1") (pin "PWR@1") (pinfunction "+_PWR@1") (pintype "power_in"))
      (node (ref "U13") (pin "14") (pinfunction "14_14") (pintype "passive"))
    )
    (net (code "58") (name "VBAT_SW") (class "Default")
      (node (ref "C13") (pin "A") (pinfunction "+_A") (pintype "passive"))
      (node (ref "JP7") (pin "3") (pinfunction "3_3") (pintype "passive"))
      (node (ref "S2") (pin "3") (pinfunction "S_3") (pintype "passive"))
      (node (ref "U18") (pin "1") (pinfunction "IN_1") (pintype "input"))
      (node (ref "U18") (pin "3") (pinfunction "EN_3") (pintype "input"))
    )
    (net (code "59") (name "VBUS") (class "Default")
      (node (ref "C10") (pin "1") (pinfunction "1_1") (pintype "passive"))
      (node (ref "JP7") (pin "4") (pinfunction "4_4") (pintype "passive"))
      (node (ref "R19") (pin "1") (pinfunction "1_1") (pintype "passive"))
      (node (ref "R2") (pin "2") (pinfunction "2_2") (pintype "passive"))
      (node (ref "R3") (pin "2") (pinfunction "2_2") (pintype "passive"))
      (node (ref "U17") (pin "4") (pinfunction "VIN_4") (pintype "power_in"))
      (node (ref "X1") (pin "VBUS") (pinfunction "VBUS_VBUS") (pintype "bidirectional"))
      (node (ref "X2") (pin "VBUS") (pinfunction "VBUS_VBUS") (pintype "bidirectional"))
    )
    (net (code "60") (name "WALL") (class "Default")
      (node (ref "JP4") (pin "7") (pinfunction "7_7") (pintype "passive"))
      (node (ref "R19") (pin "2") (pinfunction "2_2") (pintype "passive"))
      (node (ref "R20") (pin "1") (pinfunction "1_1") (pintype "passive"))
      (node (ref "U12") (pin "11") (pinfunction "PD7(AIN1)_11") (pintype "bidirectional"))
    )
    (net (code "61") (name "XTAL1") (class "Default")
      (node (ref "C8") (pin "1") (pinfunction "1_1") (pintype "passive"))
      (node (ref "Q1") (pin "1") (pinfunction "1_1") (pintype "passive"))
      (node (ref "U12") (pin "7") (pinfunction "PB6(XTAL1/TOSC1)_7") (pintype "bidirectional"))
    )
    (net (code "62") (name "XTAL2") (class "Default")
      (node (ref "C7") (pin "1") (pinfunction "1_1") (pintype "passive"))
      (node (ref "Q1") (pin "2") (pinfunction "2_2") (pintype "passive"))
      (node (ref "U12") (pin "8") (pinfunction "PB7(XTAL2/TOSC2)_8") (pintype "bidirectional"))
    )
    (net (code "63") (name "unconnected-(JP10-Pad2)") (class "Default")
      (node (ref "JP10") (pin "2") (pinfunction "2_2") (pintype "passive"))
    )
    (net (code "64") (name "unconnected-(S2-O-Pad1)") (class "Default")
      (node (ref "S2") (pin "1") (pinfunction "O_1") (pintype "passive"))
    )
    (net (code "65") (name "unconnected-(U7-BO-Pad3)") (class "Default")
      (node (ref "U7") (pin "3") (pinfunction "BO_3") (pintype "passive"))
    )
    (net (code "66") (name "unconnected-(U8-AIO1-Pad35)") (class "Default")
      (node (ref "U8") (pin "35") (pinfunction "AIO1_35") (pintype "bidirectional"))
    )
    (net (code "67") (name "unconnected-(U8-AIO2-Pad30)") (class "Default")
      (node (ref "U8") (pin "30") (pinfunction "AIO2_30") (pintype "bidirectional"))
    )
    (net (code "68") (name "unconnected-(U8-GND2-Pad25)") (class "Default")
      (node (ref "U8") (pin "25") (pinfunction "GND2_25") (pintype "bidirectional"))
    )
    (net (code "69") (name "unconnected-(U8-GND3-Pad27)") (class "Default")
      (node (ref "U8") (pin "27") (pinfunction "GND3_27") (pintype "bidirectional"))
    )
    (net (code "70") (name "unconnected-(U8-NC-Pad26)") (class "Default")
      (node (ref "U8") (pin "26") (pinfunction "NC_26") (pintype "bidirectional"))
    )
    (net (code "71") (name "unconnected-(U8-PCMCLK-Pad7)") (class "Default")
      (node (ref "U8") (pin "7") (pinfunction "PCMCLK_7") (pintype "bidirectional"))
    )
    (net (code "72") (name "unconnected-(U8-PCMIN-Pad9)") (class "Default")
      (node (ref "U8") (pin "9") (pinfunction "PCMIN_9") (pintype "bidirectional"))
    )
    (net (code "73") (name "unconnected-(U8-PCMOUT-Pad10)") (class "Default")
      (node (ref "U8") (pin "10") (pinfunction "PCMOUT_10") (pintype "bidirectional"))
    )
    (net (code "74") (name "unconnected-(U8-PCMSYNC-Pad8)") (class "Default")
      (node (ref "U8") (pin "8") (pinfunction "PCMSYNC_8") (pintype "bidirectional"))
    )
    (net (code "75") (name "unconnected-(U8-PIO9-Pad32)") (class "Default")
      (node (ref "U8") (pin "32") (pinfunction "PIO9_32") (pintype "bidirectional"))
    )
    (net (code "76") (name "unconnected-(U8-PIO10-Pad33)") (class "Default")
      (node (ref "U8") (pin "33") (pinfunction "PIO10_33") (pintype "bidirectional"))
    )
    (net (code "77") (name "unconnected-(U8-PIO11-Pad34)") (class "Default")
      (node (ref "U8") (pin "34") (pinfunction "PIO11_34") (pintype "bidirectional"))
    )
    (net (code "78") (name "unconnected-(U8-USBD+-Pad17)") (class "Default")
      (node (ref "U8") (pin "17") (pinfunction "USBD+_17") (pintype "bidirectional"))
    )
    (net (code "79") (name "unconnected-(U8-USBD--Pad18)") (class "Default")
      (node (ref "U8") (pin "18") (pinfunction "USBD-_18") (pintype "bidirectional"))
    )
    (net (code "80") (name "unconnected-(U18-BP-Pad4)") (class "Default")
      (node (ref "U18") (pin "4") (pinfunction "BP_4") (pintype "input"))
    )
    (net (code "81") (name "unconnected-(U19-NC-Pad1)") (class "Default")
      (node (ref "U19") (pin "1") (pinfunction "NC_1") (pintype "bidirectional"))
    )
    (net (code "82") (name "unconnected-(U19-PadCD1)") (class "Default")
      (node (ref "U19") (pin "CD1") (pinfunction "CD1_CD1") (pintype "bidirectional"))
    )
    (net (code "83") (name "unconnected-(U19-PadCD2)") (class "Default")
      (node (ref "U19") (pin "CD2") (pinfunction "CD2_CD2") (pintype "bidirectional"))
    )
    (net (code "84") (name "unconnected-(U19-RSV-Pad8)") (class "Default")
      (node (ref "U19") (pin "8") (pinfunction "RSV_8") (pintype "bidirectional"))
    )
  )
)
